# RocketometerATMega.net
KiCad netlist of a schematic drawn in EAGLE
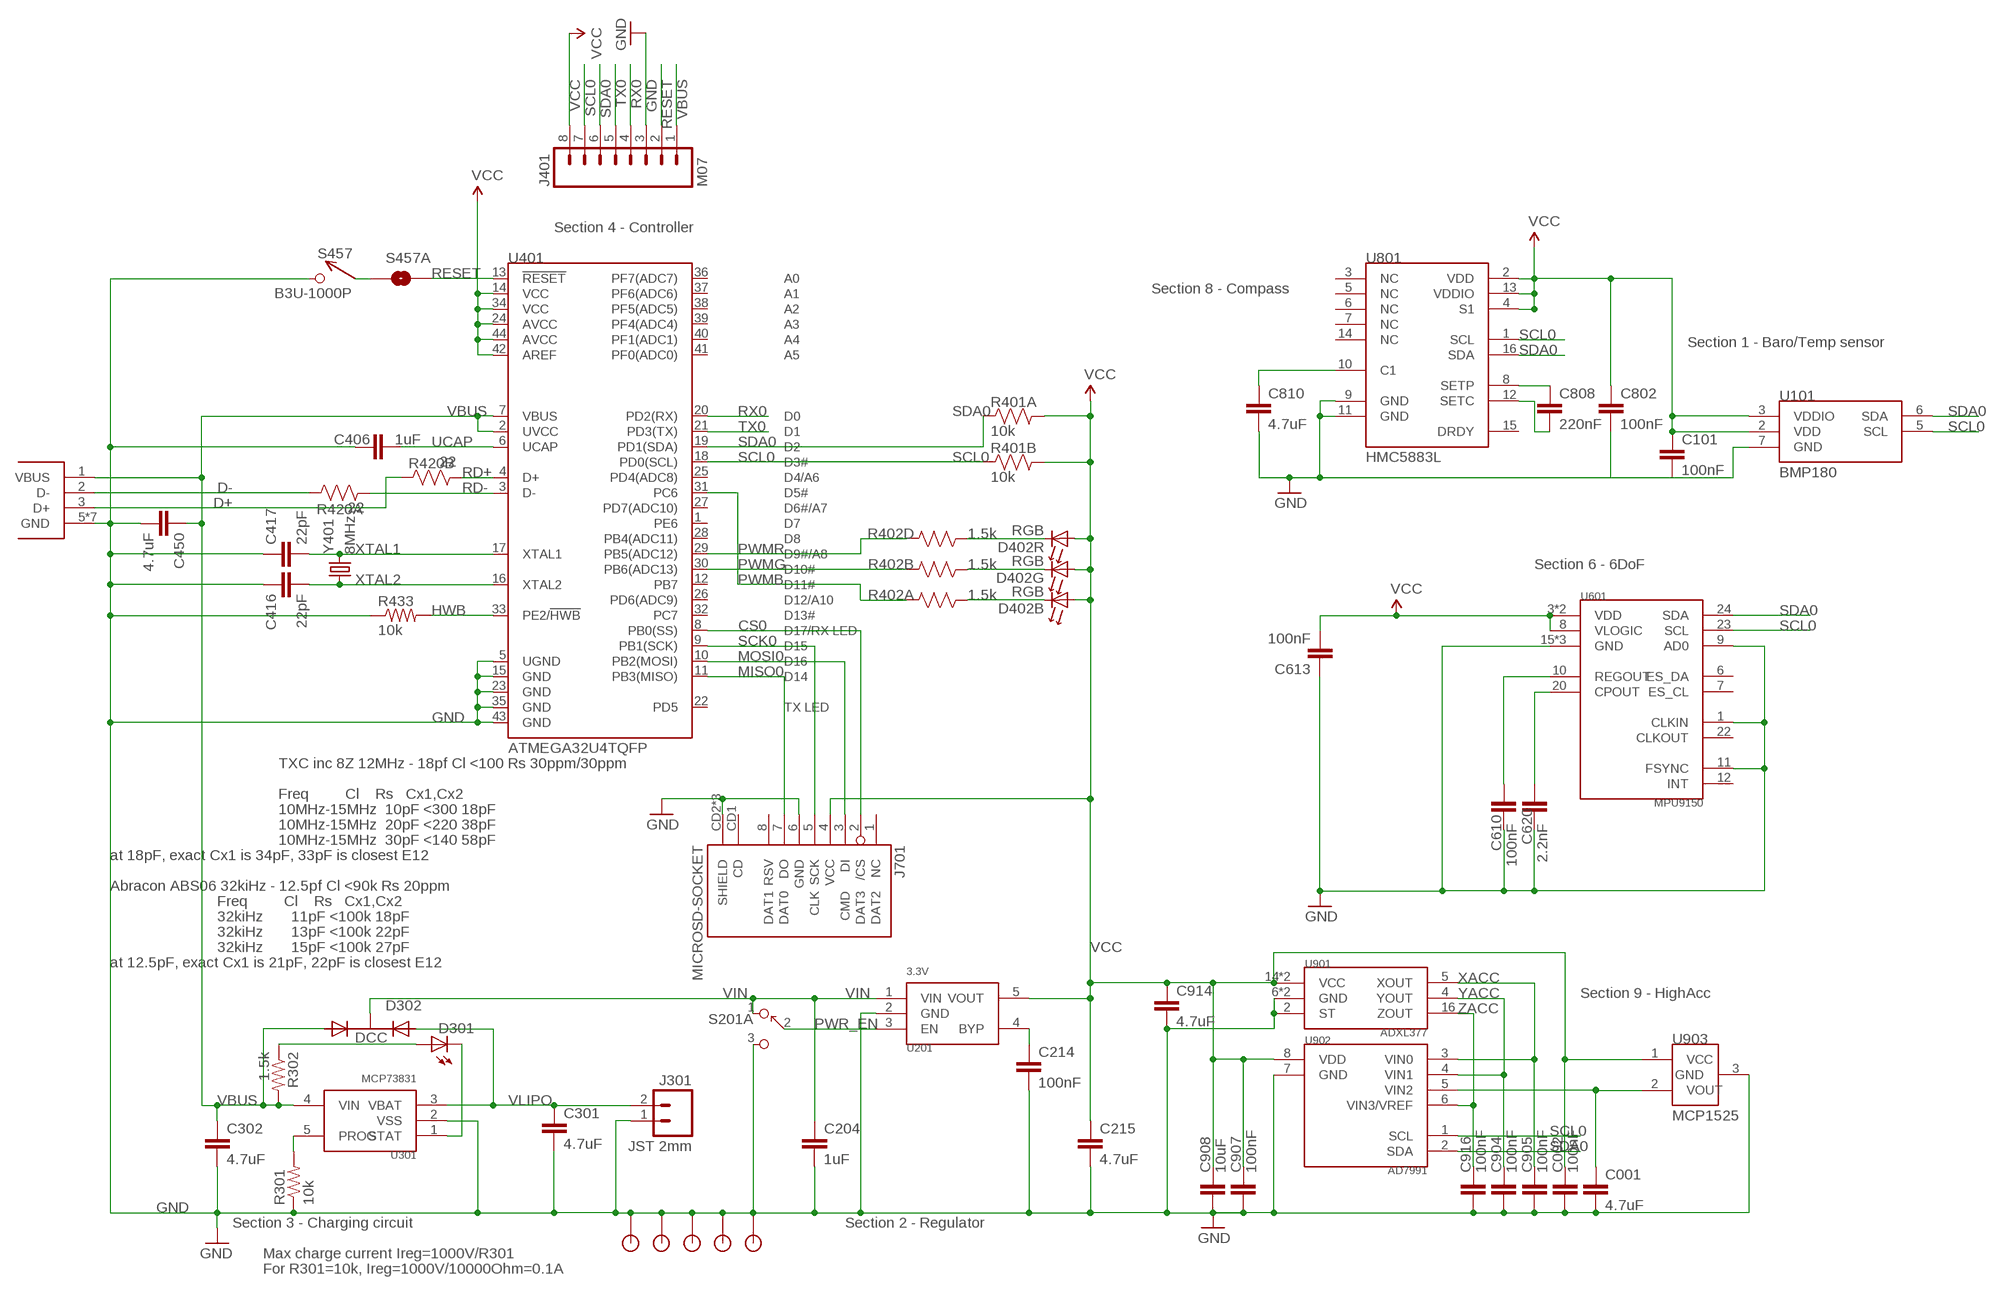
[diagram p0: schematic, sheet 1]

(export (version "E")
  (design (tool "Eeschema 10.0.6"))
  (components
    (comp (ref "C001")
      (value "4.7uF")
      (footprint "eagle-import:0402-CAP")
      (libsource (lib "eagle-import") (part "CAP0402-CAP"))
    )
    (comp (ref "C002")
      (value "100nF")
      (footprint "eagle-import:0402-CAP")
      (libsource (lib "eagle-import") (part "SparkFun-Passives_CAP0402-CAP"))
    )
    (comp (ref "C101")
      (value "100nF")
      (footprint "eagle-import:0402-CAP")
      (libsource (lib "eagle-import") (part "CAP0402-CAP"))
    )
    (comp (ref "C204")
      (value "1uF")
      (footprint "eagle-import:0402-CAP")
      (libsource (lib "eagle-import") (part "CAP0402-CAP"))
    )
    (comp (ref "C214")
      (value "100nF")
      (footprint "eagle-import:0402-CAP")
      (libsource (lib "eagle-import") (part "CAP0402-CAP"))
    )
    (comp (ref "C215")
      (value "4.7uF")
      (footprint "eagle-import:0402-CAP")
      (libsource (lib "eagle-import") (part "CAP0402-CAP"))
    )
    (comp (ref "C301")
      (value "4.7uF")
      (footprint "eagle-import:0402-CAP")
      (libsource (lib "eagle-import") (part "CAP0402-CAP"))
    )
    (comp (ref "C302")
      (value "4.7uF")
      (footprint "eagle-import:0402-CAP")
      (libsource (lib "eagle-import") (part "CAP0402-CAP"))
    )
    (comp (ref "C406")
      (value "1uF")
      (footprint "eagle-import:0402-CAP")
      (libsource (lib "eagle-import") (part "SparkFun-Passives_CAP0402-CAP"))
    )
    (comp (ref "C416")
      (value "22pF")
      (footprint "eagle-import:0402-CAP")
      (libsource (lib "eagle-import") (part "CAP0402-CAP"))
    )
    (comp (ref "C417")
      (value "22pF")
      (footprint "eagle-import:0402-CAP")
      (libsource (lib "eagle-import") (part "CAP0402-CAP"))
    )
    (comp (ref "C450")
      (value "4.7uF")
      (footprint "eagle-import:0402-CAP")
      (libsource (lib "eagle-import") (part "SparkFun-Passives_CAP0402-CAP"))
    )
    (comp (ref "C610")
      (value "100nF")
      (footprint "eagle-import:0402-CAP")
      (libsource (lib "eagle-import") (part "CAP0402-CAP"))
    )
    (comp (ref "C613")
      (value "100nF")
      (footprint "eagle-import:0402-CAP")
      (libsource (lib "eagle-import") (part "CAP0402-CAP"))
    )
    (comp (ref "C620")
      (value "2.2nF")
      (footprint "eagle-import:0402-CAP")
      (libsource (lib "eagle-import") (part "CAP0402-CAP"))
    )
    (comp (ref "C802")
      (value "100nF")
      (footprint "eagle-import:0402-CAP")
      (libsource (lib "eagle-import") (part "CAP0402-CAP"))
    )
    (comp (ref "C808")
      (value "220nF")
      (footprint "eagle-import:0402-CAP")
      (libsource (lib "eagle-import") (part "CAP0402-CAP"))
    )
    (comp (ref "C810")
      (value "4.7uF")
      (footprint "eagle-import:0402-CAP")
      (libsource (lib "eagle-import") (part "CAP0402-CAP"))
    )
    (comp (ref "C904")
      (value "100nF")
      (footprint "eagle-import:0402-CAP")
      (libsource (lib "eagle-import") (part "CAP0402-CAP"))
    )
    (comp (ref "C905")
      (value "100nF")
      (footprint "eagle-import:0402-CAP")
      (libsource (lib "eagle-import") (part "CAP0402-CAP"))
    )
    (comp (ref "C907")
      (value "100nF")
      (footprint "eagle-import:0402-CAP")
      (libsource (lib "eagle-import") (part "SparkFun-Passives_CAP0402-CAP"))
    )
    (comp (ref "C908")
      (value "10uF")
      (footprint "eagle-import:0603-CAP")
      (libsource (lib "eagle-import") (part "CAP0603-CAP"))
    )
    (comp (ref "C914")
      (value "4.7uF")
      (footprint "eagle-import:0402-CAP")
      (libsource (lib "eagle-import") (part "CAP0402-CAP"))
    )
    (comp (ref "C916")
      (value "100nF")
      (footprint "eagle-import:0402-CAP")
      (libsource (lib "eagle-import") (part "CAP0402-CAP"))
    )
    (comp (ref "D301")
      (value "YELLOW")
      (footprint "eagle-import:LED-0603")
      (libsource (lib "eagle-import") (part "LED0603"))
    )
    (comp (ref "D302")
      (value "DCC")
      (footprint "eagle-import:SOT-23-3")
      (libsource (lib "eagle-import") (part "PMEG2005CT"))
    )
    (comp (ref "D402")
      (value "RGB")
      (footprint "eagle-import:SMLP36")
      (fields (field (name "DIGIKEY") "846-1097-1-ND"))
      (libsource (lib "eagle-import") (part "SMLP36RGB2W(R)"))
    )
    (comp (ref "J301")
      (value "JST 2mm")
      (footprint "eagle-import:JST-2-SMD")
      (libsource (lib "eagle-import") (part "M02-JST-2MM-SMT"))
    )
    (comp (ref "J400")
      (value "USB_MICROB_JSTGCT")
      (footprint "eagle-import:USB_MICROB_3075")
      (libsource (lib "eagle-import") (part "USB_MICROB_JSTGCT"))
    )
    (comp (ref "J401")
      (value "M07")
      (footprint "eagle-import:1X08")
      (libsource (lib "eagle-import") (part "M081X08"))
    )
    (comp (ref "J701")
      (value "MICROSD-SOCKET")
      (footprint "eagle-import:MICROSD-SOCKET-PP")
      (libsource (lib "eagle-import") (part "MICROSD-SOCKET"))
    )
    (comp (ref "JP1")
      (value "STANDOFF")
      (footprint "eagle-import:STANDOFF")
      (libsource (lib "eagle-import") (part "STANDOFF"))
    )
    (comp (ref "JP2")
      (value "STANDOFF")
      (footprint "eagle-import:STANDOFF")
      (libsource (lib "eagle-import") (part "STANDOFF"))
    )
    (comp (ref "JP3")
      (value "STANDOFF")
      (footprint "eagle-import:STANDOFF")
      (libsource (lib "eagle-import") (part "STANDOFF"))
    )
    (comp (ref "JP4")
      (value "STANDOFF")
      (footprint "eagle-import:STANDOFF")
      (libsource (lib "eagle-import") (part "STANDOFF"))
    )
    (comp (ref "JP5")
      (value "STANDOFF")
      (footprint "eagle-import:STANDOFF")
      (libsource (lib "eagle-import") (part "STANDOFF"))
    )
    (comp (ref "R301")
      (value "10k")
      (footprint "eagle-import:0402-RES")
      (libsource (lib "eagle-import") (part "RESISTOR0402-RES"))
    )
    (comp (ref "R302")
      (value "1.5k")
      (footprint "eagle-import:0402-RES")
      (libsource (lib "eagle-import") (part "RESISTOR0402-RES"))
    )
    (comp (ref "R401")
      (value "10k")
      (footprint "eagle-import:CRA02")
      (fields (field (name "DIGIKEY") "Y5103CT-ND"))
      (libsource (lib "eagle-import") (part "RP2EXB24V"))
    )
    (comp (ref "R402")
      (value "1.5k")
      (footprint "eagle-import:CRA04")
      (fields (field (name "DIGIKEY") "CRA4S81.5KCT-ND"))
      (libsource (lib "eagle-import") (part "RP404"))
    )
    (comp (ref "R420")
      (value "22")
      (footprint "eagle-import:CRA02")
      (fields (field (name "DIGIKEY") "Y5220CT-ND"))
      (libsource (lib "eagle-import") (part "RP2EXB24V"))
    )
    (comp (ref "R433")
      (value "10k")
      (footprint "eagle-import:0402-RES")
      (libsource (lib "eagle-import") (part "SparkFun-Passives_RESISTOR0402-RES"))
    )
    (comp (ref "S201")
      (value "AYZ0202")
      (footprint "eagle-import:AYZ0202")
      (libsource (lib "eagle-import") (part "AYZ0202"))
    )
    (comp (ref "S457")
      (value "B3U-1000P")
      (footprint "eagle-import:B3U-1000P")
      (libsource (lib "eagle-import") (part "B3U-1000P"))
    )
    (comp (ref "S457A")
      (value "SOLDERJUMPERNO")
      (footprint "eagle-import:SJ_2S-NO")
      (libsource (lib "eagle-import") (part "SOLDERJUMPERNO"))
    )
    (comp (ref "U101")
      (value "BMP180")
      (footprint "eagle-import:BMP180")
      (libsource (lib "eagle-import") (part "BMP180"))
    )
    (comp (ref "U201")
      (value "3.3V")
      (footprint "eagle-import:SOT-23-5")
      (libsource (lib "eagle-import") (part "MIC5319D5"))
    )
    (comp (ref "U301")
      (value "MCP73831")
      (footprint "eagle-import:SOT-23-5")
      (libsource (lib "eagle-import") (part "MCP73831"))
    )
    (comp (ref "U401")
      (value "ATMEGA32U4TQFP")
      (footprint "eagle-import:SPARKFUN-DIGITALIC_TQFP44")
      (libsource (lib "eagle-import") (part "ATMEGA32U4TQFP"))
    )
    (comp (ref "U601")
      (value "MPU9150")
      (footprint "eagle-import:LLGA24")
      (libsource (lib "eagle-import") (part "MPU9150"))
    )
    (comp (ref "U801")
      (value "HMC5883L")
      (footprint "eagle-import:16LPCC")
      (libsource (lib "eagle-import") (part "HMC5883LSMD"))
    )
    (comp (ref "U901")
      (value "ADXL377")
      (footprint "eagle-import:ADXL377")
      (libsource (lib "eagle-import") (part "ADXL377"))
    )
    (comp (ref "U902")
      (value "AD7991")
      (footprint "eagle-import:SOT-23-8")
      (libsource (lib "eagle-import") (part "AD799X"))
    )
    (comp (ref "U903")
      (value "MCP1525")
      (footprint "eagle-import:SOT-23-3")
      (libsource (lib "eagle-import") (part "MCP1525"))
    )
    (comp (ref "Y401")
      (value "8MHz")
      (footprint "eagle-import:CRYSTAL_SMD_3_2MM_2_5MM")
      (libsource (lib "eagle-import") (part "NX3225GD"))
    )
  )
  (nets
    (net (code "1") (name "/CS0") (class "Default")
      (node (ref "J701") (pin "2") (pinfunction "/CS_2") (pintype "bidirectional"))
      (node (ref "U401") (pin "8") (pinfunction "PB0(SS)_8") (pintype "bidirectional"))
    )
    (net (code "2") (name "/D+") (class "Default")
      (node (ref "J400") (pin "3") (pinfunction "D+_3") (pintype "bidirectional"))
      (node (ref "R420") (pin "2") (pinfunction "1_2") (pintype "passive"))
    )
    (net (code "3") (name "/D-") (class "Default")
      (node (ref "J400") (pin "2") (pinfunction "D-_2") (pintype "bidirectional"))
      (node (ref "R420") (pin "1") (pinfunction "1_1") (pintype "passive"))
    )
    (net (code "4") (name "/HWB") (class "Default")
      (node (ref "R433") (pin "2") (pinfunction "2_2") (pintype "passive"))
      (node (ref "U401") (pin "33") (pinfunction "PE2/~{HWB}_33") (pintype "bidirectional"))
    )
    (net (code "5") (name "/MISO0") (class "Default")
      (node (ref "J701") (pin "7") (pinfunction "DO_7") (pintype "bidirectional"))
      (node (ref "U401") (pin "11") (pinfunction "PB3(MISO)_11") (pintype "bidirectional"))
    )
    (net (code "6") (name "/MOSI0") (class "Default")
      (node (ref "J701") (pin "3") (pinfunction "DI_3") (pintype "bidirectional"))
      (node (ref "U401") (pin "10") (pinfunction "PB2(MOSI)_10") (pintype "bidirectional"))
    )
    (net (code "7") (name "/PWMB") (class "Default")
      (node (ref "R402") (pin "8") (pinfunction "2_8") (pintype "passive"))
      (node (ref "U401") (pin "31") (pinfunction "PC6_31") (pintype "bidirectional"))
    )
    (net (code "8") (name "/PWMG") (class "Default")
      (node (ref "R402") (pin "7") (pinfunction "2_7") (pintype "passive"))
      (node (ref "U401") (pin "30") (pinfunction "PB6(ADC13)_30") (pintype "bidirectional"))
    )
    (net (code "9") (name "/PWMR") (class "Default")
      (node (ref "R402") (pin "5") (pinfunction "2_5") (pintype "passive"))
      (node (ref "U401") (pin "29") (pinfunction "PB5(ADC12)_29") (pintype "bidirectional"))
    )
    (net (code "10") (name "/PWR_EN") (class "Default")
      (node (ref "S201") (pin "2") (pinfunction "P$3_2") (pintype "bidirectional"))
      (node (ref "U201") (pin "3") (pinfunction "EN_3") (pintype "bidirectional"))
    )
    (net (code "11") (name "/RD+") (class "Default")
      (node (ref "R420") (pin "3") (pinfunction "2_3") (pintype "passive"))
      (node (ref "U401") (pin "4") (pinfunction "D+_4") (pintype "bidirectional"))
    )
    (net (code "12") (name "/RD-") (class "Default")
      (node (ref "R420") (pin "4") (pinfunction "2_4") (pintype "passive"))
      (node (ref "U401") (pin "3") (pinfunction "D-_3") (pintype "bidirectional"))
    )
    (net (code "13") (name "/RESET") (class "Default")
      (node (ref "J401") (pin "2") (pinfunction "2_2") (pintype "passive"))
      (node (ref "S457A") (pin "2") (pinfunction "2_2") (pintype "passive"))
      (node (ref "U401") (pin "13") (pinfunction "~{RESET}_13") (pintype "bidirectional"))
    )
    (net (code "14") (name "/RX0") (class "Default")
      (node (ref "J401") (pin "4") (pinfunction "4_4") (pintype "passive"))
      (node (ref "U401") (pin "20") (pinfunction "PD2(RX)_20") (pintype "bidirectional"))
    )
    (net (code "15") (name "/SCK0") (class "Default")
      (node (ref "J701") (pin "5") (pinfunction "SCK_5") (pintype "bidirectional"))
      (node (ref "U401") (pin "9") (pinfunction "PB1(SCK)_9") (pintype "bidirectional"))
    )
    (net (code "16") (name "/SCL0") (class "Default")
      (node (ref "J401") (pin "7") (pinfunction "7_7") (pintype "passive"))
      (node (ref "R401") (pin "2") (pinfunction "1_2") (pintype "passive"))
      (node (ref "U101") (pin "5") (pinfunction "SCL_5") (pintype "input"))
      (node (ref "U401") (pin "18") (pinfunction "PD0(SCL)_18") (pintype "bidirectional"))
      (node (ref "U601") (pin "23") (pinfunction "SCL_23") (pintype "bidirectional"))
      (node (ref "U801") (pin "1") (pinfunction "SCL_1") (pintype "bidirectional"))
      (node (ref "U902") (pin "1") (pinfunction "SCL_1") (pintype "bidirectional"))
    )
    (net (code "17") (name "/SDA0") (class "Default")
      (node (ref "J401") (pin "6") (pinfunction "6_6") (pintype "passive"))
      (node (ref "R401") (pin "1") (pinfunction "1_1") (pintype "passive"))
      (node (ref "U101") (pin "6") (pinfunction "SDA_6") (pintype "bidirectional"))
      (node (ref "U401") (pin "19") (pinfunction "PD1(SDA)_19") (pintype "bidirectional"))
      (node (ref "U601") (pin "24") (pinfunction "SDA_24") (pintype "bidirectional"))
      (node (ref "U801") (pin "16") (pinfunction "SDA_16") (pintype "bidirectional"))
      (node (ref "U902") (pin "2") (pinfunction "SDA_2") (pintype "bidirectional"))
    )
    (net (code "18") (name "/TX0") (class "Default")
      (node (ref "J401") (pin "5") (pinfunction "5_5") (pintype "passive"))
      (node (ref "U401") (pin "21") (pinfunction "PD3(TX)_21") (pintype "bidirectional"))
    )
    (net (code "19") (name "/UCAP") (class "Default")
      (node (ref "C406") (pin "1") (pinfunction "1_1") (pintype "passive"))
      (node (ref "U401") (pin "6") (pinfunction "UCAP_6") (pintype "bidirectional"))
    )
    (net (code "20") (name "/VBUS") (class "Default")
      (node (ref "C302") (pin "1") (pinfunction "1_1") (pintype "passive"))
      (node (ref "C450") (pin "1") (pinfunction "1_1") (pintype "passive"))
      (node (ref "D302") (pin "1") (pinfunction "A1_1") (pintype "passive"))
      (node (ref "J400") (pin "1") (pinfunction "VBUS_1") (pintype "bidirectional"))
      (node (ref "J401") (pin "1") (pinfunction "1_1") (pintype "passive"))
      (node (ref "R302") (pin "2") (pinfunction "2_2") (pintype "passive"))
      (node (ref "U301") (pin "4") (pinfunction "VIN_4") (pintype "power_in"))
      (node (ref "U401") (pin "2") (pinfunction "UVCC_2") (pintype "bidirectional"))
      (node (ref "U401") (pin "7") (pinfunction "VBUS_7") (pintype "bidirectional"))
    )
    (net (code "21") (name "/VIN") (class "Default")
      (node (ref "C204") (pin "1") (pinfunction "1_1") (pintype "passive"))
      (node (ref "D302") (pin "3") (pinfunction "K_3") (pintype "passive"))
      (node (ref "S201") (pin "1") (pinfunction "P$1_1") (pintype "bidirectional"))
      (node (ref "U201") (pin "1") (pinfunction "VIN_1") (pintype "bidirectional"))
    )
    (net (code "22") (name "/VLIPO") (class "Default")
      (node (ref "C301") (pin "1") (pinfunction "1_1") (pintype "passive"))
      (node (ref "D302") (pin "2") (pinfunction "A2_2") (pintype "passive"))
      (node (ref "J301") (pin "2") (pinfunction "2_2") (pintype "passive"))
      (node (ref "U301") (pin "3") (pinfunction "VBAT_3") (pintype "power_in"))
    )
    (net (code "23") (name "/XACC") (class "Default")
      (node (ref "C905") (pin "1") (pinfunction "1_1") (pintype "passive"))
      (node (ref "U901") (pin "5") (pinfunction "XOUT_5") (pintype "bidirectional"))
      (node (ref "U902") (pin "3") (pinfunction "VIN0_3") (pintype "bidirectional"))
    )
    (net (code "24") (name "/XTAL1") (class "Default")
      (node (ref "C417") (pin "2") (pinfunction "2_2") (pintype "passive"))
      (node (ref "U401") (pin "17") (pinfunction "XTAL1_17") (pintype "bidirectional"))
      (node (ref "Y401") (pin "2") (pinfunction "2_2") (pintype "passive"))
    )
    (net (code "25") (name "/XTAL2") (class "Default")
      (node (ref "C416") (pin "2") (pinfunction "2_2") (pintype "passive"))
      (node (ref "U401") (pin "16") (pinfunction "XTAL2_16") (pintype "bidirectional"))
      (node (ref "Y401") (pin "1") (pinfunction "1_1") (pintype "passive"))
    )
    (net (code "26") (name "/YACC") (class "Default")
      (node (ref "C904") (pin "1") (pinfunction "1_1") (pintype "passive"))
      (node (ref "U901") (pin "4") (pinfunction "YOUT_4") (pintype "bidirectional"))
      (node (ref "U902") (pin "4") (pinfunction "VIN1_4") (pintype "bidirectional"))
    )
    (net (code "27") (name "/ZACC") (class "Default")
      (node (ref "C916") (pin "1") (pinfunction "1_1") (pintype "passive"))
      (node (ref "U901") (pin "16") (pinfunction "ZOUT_16") (pintype "bidirectional"))
      (node (ref "U902") (pin "6") (pinfunction "VIN3/VREF_6") (pintype "bidirectional"))
    )
    (net (code "28") (name "GND") (class "Default")
      (node (ref "C001") (pin "2") (pinfunction "2_2") (pintype "passive"))
      (node (ref "C002") (pin "2") (pinfunction "2_2") (pintype "passive"))
      (node (ref "C101") (pin "2") (pinfunction "2_2") (pintype "passive"))
      (node (ref "C204") (pin "2") (pinfunction "2_2") (pintype "passive"))
      (node (ref "C214") (pin "2") (pinfunction "2_2") (pintype "passive"))
      (node (ref "C215") (pin "2") (pinfunction "2_2") (pintype "passive"))
      (node (ref "C301") (pin "2") (pinfunction "2_2") (pintype "passive"))
      (node (ref "C302") (pin "2") (pinfunction "2_2") (pintype "passive"))
      (node (ref "C406") (pin "2") (pinfunction "2_2") (pintype "passive"))
      (node (ref "C416") (pin "1") (pinfunction "1_1") (pintype "passive"))
      (node (ref "C417") (pin "1") (pinfunction "1_1") (pintype "passive"))
      (node (ref "C450") (pin "2") (pinfunction "2_2") (pintype "passive"))
      (node (ref "C610") (pin "2") (pinfunction "2_2") (pintype "passive"))
      (node (ref "C613") (pin "1") (pinfunction "1_1") (pintype "passive"))
      (node (ref "C620") (pin "1") (pinfunction "1_1") (pintype "passive"))
      (node (ref "C802") (pin "2") (pinfunction "2_2") (pintype "passive"))
      (node (ref "C810") (pin "2") (pinfunction "2_2") (pintype "passive"))
      (node (ref "C904") (pin "2") (pinfunction "2_2") (pintype "passive"))
      (node (ref "C905") (pin "2") (pinfunction "2_2") (pintype "passive"))
      (node (ref "C907") (pin "2") (pinfunction "2_2") (pintype "passive"))
      (node (ref "C908") (pin "2") (pinfunction "2_2") (pintype "passive"))
      (node (ref "C914") (pin "2") (pinfunction "2_2") (pintype "passive"))
      (node (ref "C916") (pin "2") (pinfunction "2_2") (pintype "passive"))
      (node (ref "J301") (pin "1") (pinfunction "1_1") (pintype "passive"))
      (node (ref "J400") (pin "5") (pinfunction "GND_5") (pintype "bidirectional"))
      (node (ref "J400") (pin "P$1") (pinfunction "GND_P$1") (pintype "bidirectional"))
      (node (ref "J400") (pin "P$10") (pinfunction "GND_P$10") (pintype "bidirectional"))
      (node (ref "J400") (pin "P$2") (pinfunction "GND_P$2") (pintype "bidirectional"))
      (node (ref "J400") (pin "P$3") (pinfunction "GND_P$3") (pintype "bidirectional"))
      (node (ref "J400") (pin "P$4") (pinfunction "GND_P$4") (pintype "bidirectional"))
      (node (ref "J400") (pin "P$8") (pinfunction "GND_P$8") (pintype "bidirectional"))
      (node (ref "J401") (pin "3") (pinfunction "3_3") (pintype "passive"))
      (node (ref "J701") (pin "6") (pinfunction "GND_6") (pintype "bidirectional"))
      (node (ref "J701") (pin "CD2") (pinfunction "SHIELD_CD2") (pintype "bidirectional"))
      (node (ref "J701") (pin "GND1") (pinfunction "SHIELD_GND1") (pintype "bidirectional"))
      (node (ref "J701") (pin "GND3") (pinfunction "SHIELD_GND3") (pintype "bidirectional"))
      (node (ref "JP1") (pin "P$1") (pinfunction "P$1_P$1") (pintype "bidirectional"))
      (node (ref "JP2") (pin "P$1") (pinfunction "P$1_P$1") (pintype "bidirectional"))
      (node (ref "JP3") (pin "P$1") (pinfunction "P$1_P$1") (pintype "bidirectional"))
      (node (ref "JP4") (pin "P$1") (pinfunction "P$1_P$1") (pintype "bidirectional"))
      (node (ref "JP5") (pin "P$1") (pinfunction "P$1_P$1") (pintype "bidirectional"))
      (node (ref "R301") (pin "1") (pinfunction "1_1") (pintype "passive"))
      (node (ref "R433") (pin "1") (pinfunction "1_1") (pintype "passive"))
      (node (ref "S201") (pin "3") (pinfunction "P$2_3") (pintype "bidirectional"))
      (node (ref "S457") (pin "P$2") (pinfunction "2_P$2") (pintype "bidirectional"))
      (node (ref "U101") (pin "7") (pinfunction "GND_7") (pintype "power_in"))
      (node (ref "U201") (pin "2") (pinfunction "GND_2") (pintype "bidirectional"))
      (node (ref "U301") (pin "2") (pinfunction "VSS_2") (pintype "power_in"))
      (node (ref "U401") (pin "15") (pinfunction "GND_15") (pintype "bidirectional"))
      (node (ref "U401") (pin "23") (pinfunction "GND_23") (pintype "bidirectional"))
      (node (ref "U401") (pin "35") (pinfunction "GND_35") (pintype "bidirectional"))
      (node (ref "U401") (pin "43") (pinfunction "GND_43") (pintype "bidirectional"))
      (node (ref "U401") (pin "5") (pinfunction "UGND_5") (pintype "bidirectional"))
      (node (ref "U601") (pin "1") (pinfunction "CLKIN_1") (pintype "bidirectional"))
      (node (ref "U601") (pin "11") (pinfunction "FSYNC_11") (pintype "bidirectional"))
      (node (ref "U601") (pin "15") (pinfunction "GND_15") (pintype "bidirectional"))
      (node (ref "U601") (pin "17") (pinfunction "GND_17") (pintype "bidirectional"))
      (node (ref "U601") (pin "18") (pinfunction "GND_18") (pintype "bidirectional"))
      (node (ref "U601") (pin "9") (pinfunction "AD0_9") (pintype "bidirectional"))
      (node (ref "U801") (pin "11") (pinfunction "GND_11") (pintype "bidirectional"))
      (node (ref "U801") (pin "9") (pinfunction "GND_9") (pintype "bidirectional"))
      (node (ref "U901") (pin "2") (pinfunction "ST_2") (pintype "bidirectional"))
      (node (ref "U901") (pin "6") (pinfunction "GND_6") (pintype "bidirectional"))
      (node (ref "U901") (pin "7") (pinfunction "GND_7") (pintype "bidirectional"))
      (node (ref "U902") (pin "7") (pinfunction "GND_7") (pintype "bidirectional"))
      (node (ref "U903") (pin "3") (pinfunction "GND_3") (pintype "bidirectional"))
    )
    (net (code "29") (name "Net-(D301-PadA)") (class "Default")
      (node (ref "D301") (pin "A") (pinfunction "A_A") (pintype "passive"))
      (node (ref "R302") (pin "1") (pinfunction "1_1") (pintype "passive"))
    )
    (net (code "30") (name "Net-(D402A-C)") (class "Default")
      (node (ref "D402") (pin "1") (pinfunction "C_1") (pintype "passive"))
      (node (ref "R402") (pin "1") (pinfunction "1_1") (pintype "passive"))
    )
    (net (code "31") (name "Net-(D402B-C)") (class "Default")
      (node (ref "D402") (pin "3") (pinfunction "C_3") (pintype "passive"))
      (node (ref "R402") (pin "2") (pinfunction "1_2") (pintype "passive"))
    )
    (net (code "32") (name "Net-(D402C-C)") (class "Default")
      (node (ref "D402") (pin "5") (pinfunction "C_5") (pintype "passive"))
      (node (ref "R402") (pin "4") (pinfunction "1_4") (pintype "passive"))
    )
    (net (code "33") (name "Net-(S457-1)") (class "Default")
      (node (ref "S457") (pin "P$1") (pinfunction "1_P$1") (pintype "bidirectional"))
      (node (ref "S457A") (pin "1") (pinfunction "1_1") (pintype "passive"))
    )
    (net (code "34") (name "Net-(U201-BYP)") (class "Default")
      (node (ref "C214") (pin "1") (pinfunction "1_1") (pintype "passive"))
      (node (ref "U201") (pin "4") (pinfunction "BYP_4") (pintype "bidirectional"))
    )
    (net (code "35") (name "Net-(U301-PROG)") (class "Default")
      (node (ref "R301") (pin "2") (pinfunction "2_2") (pintype "passive"))
      (node (ref "U301") (pin "5") (pinfunction "PROG_5") (pintype "passive"))
    )
    (net (code "36") (name "Net-(U301-STAT)") (class "Default")
      (node (ref "D301") (pin "C") (pinfunction "C_C") (pintype "passive"))
      (node (ref "U301") (pin "1") (pinfunction "STAT_1") (pintype "bidirectional"))
    )
    (net (code "37") (name "Net-(U601-CPOUT)") (class "Default")
      (node (ref "C620") (pin "2") (pinfunction "2_2") (pintype "passive"))
      (node (ref "U601") (pin "20") (pinfunction "CPOUT_20") (pintype "bidirectional"))
    )
    (net (code "38") (name "Net-(U601-REGOUT)") (class "Default")
      (node (ref "C610") (pin "1") (pinfunction "1_1") (pintype "passive"))
      (node (ref "U601") (pin "10") (pinfunction "REGOUT_10") (pintype "bidirectional"))
    )
    (net (code "39") (name "Net-(U801-C1)") (class "Default")
      (node (ref "C810") (pin "1") (pinfunction "1_1") (pintype "passive"))
      (node (ref "U801") (pin "10") (pinfunction "C1_10") (pintype "bidirectional"))
    )
    (net (code "40") (name "Net-(U801-SETC)") (class "Default")
      (node (ref "C808") (pin "2") (pinfunction "2_2") (pintype "passive"))
      (node (ref "U801") (pin "12") (pinfunction "SETC_12") (pintype "bidirectional"))
    )
    (net (code "41") (name "Net-(U801-SETP)") (class "Default")
      (node (ref "C808") (pin "1") (pinfunction "1_1") (pintype "passive"))
      (node (ref "U801") (pin "8") (pinfunction "SETP_8") (pintype "bidirectional"))
    )
    (net (code "42") (name "Net-(U902-VIN2)") (class "Default")
      (node (ref "C001") (pin "1") (pinfunction "1_1") (pintype "passive"))
      (node (ref "U902") (pin "5") (pinfunction "VIN2_5") (pintype "bidirectional"))
      (node (ref "U903") (pin "2") (pinfunction "VOUT_2") (pintype "bidirectional"))
    )
    (net (code "43") (name "VCC") (class "Default")
      (node (ref "C002") (pin "1") (pinfunction "1_1") (pintype "passive"))
      (node (ref "C101") (pin "1") (pinfunction "1_1") (pintype "passive"))
      (node (ref "C215") (pin "1") (pinfunction "1_1") (pintype "passive"))
      (node (ref "C613") (pin "2") (pinfunction "2_2") (pintype "passive"))
      (node (ref "C802") (pin "1") (pinfunction "1_1") (pintype "passive"))
      (node (ref "C907") (pin "1") (pinfunction "1_1") (pintype "passive"))
      (node (ref "C908") (pin "1") (pinfunction "1_1") (pintype "passive"))
      (node (ref "C914") (pin "1") (pinfunction "1_1") (pintype "passive"))
      (node (ref "D402") (pin "2") (pinfunction "A_2") (pintype "passive"))
      (node (ref "D402") (pin "4") (pinfunction "A_4") (pintype "passive"))
      (node (ref "D402") (pin "6") (pinfunction "A_6") (pintype "passive"))
      (node (ref "J401") (pin "8") (pinfunction "8_8") (pintype "passive"))
      (node (ref "J701") (pin "4") (pinfunction "VCC_4") (pintype "bidirectional"))
      (node (ref "R401") (pin "3") (pinfunction "2_3") (pintype "passive"))
      (node (ref "R401") (pin "4") (pinfunction "2_4") (pintype "passive"))
      (node (ref "U101") (pin "2") (pinfunction "VDD_2") (pintype "power_in"))
      (node (ref "U101") (pin "3") (pinfunction "VDDIO_3") (pintype "power_in"))
      (node (ref "U201") (pin "5") (pinfunction "VOUT_5") (pintype "bidirectional"))
      (node (ref "U401") (pin "14") (pinfunction "VCC_14") (pintype "bidirectional"))
      (node (ref "U401") (pin "24") (pinfunction "AVCC_24") (pintype "bidirectional"))
      (node (ref "U401") (pin "34") (pinfunction "VCC_34") (pintype "bidirectional"))
      (node (ref "U401") (pin "42") (pinfunction "AREF_42") (pintype "bidirectional"))
      (node (ref "U401") (pin "44") (pinfunction "AVCC_44") (pintype "bidirectional"))
      (node (ref "U601") (pin "13") (pinfunction "VDD_13") (pintype "bidirectional"))
      (node (ref "U601") (pin "3") (pinfunction "VDD_3") (pintype "bidirectional"))
      (node (ref "U601") (pin "8") (pinfunction "VLOGIC_8") (pintype "bidirectional"))
      (node (ref "U801") (pin "13") (pinfunction "VDDIO_13") (pintype "bidirectional"))
      (node (ref "U801") (pin "2") (pinfunction "VDD_2") (pintype "bidirectional"))
      (node (ref "U801") (pin "4") (pinfunction "S1_4") (pintype "bidirectional"))
      (node (ref "U901") (pin "14") (pinfunction "VCC_14") (pintype "bidirectional"))
      (node (ref "U901") (pin "15") (pinfunction "VCC_15") (pintype "bidirectional"))
      (node (ref "U902") (pin "8") (pinfunction "VDD_8") (pintype "bidirectional"))
      (node (ref "U903") (pin "1") (pinfunction "VCC_1") (pintype "bidirectional"))
    )
    (net (code "44") (name "unconnected-(J701-CD-PadCD1)") (class "Default")
      (node (ref "J701") (pin "CD1") (pinfunction "CD_CD1") (pintype "bidirectional"))
    )
    (net (code "45") (name "unconnected-(J701-NC-Pad1)") (class "Default")
      (node (ref "J701") (pin "1") (pinfunction "NC_1") (pintype "bidirectional"))
    )
    (net (code "46") (name "unconnected-(J701-RSV-Pad8)") (class "Default")
      (node (ref "J701") (pin "8") (pinfunction "RSV_8") (pintype "bidirectional"))
    )
    (net (code "47") (name "unconnected-(U401-PB4(ADC11)-Pad28)") (class "Default")
      (node (ref "U401") (pin "28") (pinfunction "PB4(ADC11)_28") (pintype "bidirectional"))
    )
    (net (code "48") (name "unconnected-(U401-PB7-Pad12)") (class "Default")
      (node (ref "U401") (pin "12") (pinfunction "PB7_12") (pintype "bidirectional"))
    )
    (net (code "49") (name "unconnected-(U401-PC7-Pad32)") (class "Default")
      (node (ref "U401") (pin "32") (pinfunction "PC7_32") (pintype "bidirectional"))
    )
    (net (code "50") (name "unconnected-(U401-PD4(ADC8)-Pad25)") (class "Default")
      (node (ref "U401") (pin "25") (pinfunction "PD4(ADC8)_25") (pintype "bidirectional"))
    )
    (net (code "51") (name "unconnected-(U401-PD5-Pad22)") (class "Default")
      (node (ref "U401") (pin "22") (pinfunction "PD5_22") (pintype "bidirectional"))
    )
    (net (code "52") (name "unconnected-(U401-PD6(ADC9)-Pad26)") (class "Default")
      (node (ref "U401") (pin "26") (pinfunction "PD6(ADC9)_26") (pintype "bidirectional"))
    )
    (net (code "53") (name "unconnected-(U401-PD7(ADC10)-Pad27)") (class "Default")
      (node (ref "U401") (pin "27") (pinfunction "PD7(ADC10)_27") (pintype "bidirectional"))
    )
    (net (code "54") (name "unconnected-(U401-PE6-Pad1)") (class "Default")
      (node (ref "U401") (pin "1") (pinfunction "PE6_1") (pintype "bidirectional"))
    )
    (net (code "55") (name "unconnected-(U401-PF0(ADC0)-Pad41)") (class "Default")
      (node (ref "U401") (pin "41") (pinfunction "PF0(ADC0)_41") (pintype "bidirectional"))
    )
    (net (code "56") (name "unconnected-(U401-PF1(ADC1)-Pad40)") (class "Default")
      (node (ref "U401") (pin "40") (pinfunction "PF1(ADC1)_40") (pintype "bidirectional"))
    )
    (net (code "57") (name "unconnected-(U401-PF4(ADC4)-Pad39)") (class "Default")
      (node (ref "U401") (pin "39") (pinfunction "PF4(ADC4)_39") (pintype "bidirectional"))
    )
    (net (code "58") (name "unconnected-(U401-PF5(ADC5)-Pad38)") (class "Default")
      (node (ref "U401") (pin "38") (pinfunction "PF5(ADC5)_38") (pintype "bidirectional"))
    )
    (net (code "59") (name "unconnected-(U401-PF6(ADC6)-Pad37)") (class "Default")
      (node (ref "U401") (pin "37") (pinfunction "PF6(ADC6)_37") (pintype "bidirectional"))
    )
    (net (code "60") (name "unconnected-(U401-PF7(ADC7)-Pad36)") (class "Default")
      (node (ref "U401") (pin "36") (pinfunction "PF7(ADC7)_36") (pintype "bidirectional"))
    )
    (net (code "61") (name "unconnected-(U601-CLKOUT-Pad22)") (class "Default")
      (node (ref "U601") (pin "22") (pinfunction "CLKOUT_22") (pintype "bidirectional"))
    )
    (net (code "62") (name "unconnected-(U601-ES_CL-Pad7)") (class "Default")
      (node (ref "U601") (pin "7") (pinfunction "ES_CL_7") (pintype "bidirectional"))
    )
    (net (code "63") (name "unconnected-(U601-ES_DA-Pad6)") (class "Default")
      (node (ref "U601") (pin "6") (pinfunction "ES_DA_6") (pintype "bidirectional"))
    )
    (net (code "64") (name "unconnected-(U601-INT-Pad12)") (class "Default")
      (node (ref "U601") (pin "12") (pinfunction "INT_12") (pintype "bidirectional"))
    )
    (net (code "65") (name "unconnected-(U801-DRDY-Pad15)") (class "Default")
      (node (ref "U801") (pin "15") (pinfunction "DRDY_15") (pintype "bidirectional"))
    )
    (net (code "66") (name "unconnected-(U801-NC-Pad3)") (class "Default")
      (node (ref "U801") (pin "3") (pinfunction "NC_3") (pintype "bidirectional"))
    )
    (net (code "67") (name "unconnected-(U801-NC-Pad5)") (class "Default")
      (node (ref "U801") (pin "5") (pinfunction "NC_5") (pintype "bidirectional"))
    )
    (net (code "68") (name "unconnected-(U801-NC-Pad6)") (class "Default")
      (node (ref "U801") (pin "6") (pinfunction "NC_6") (pintype "bidirectional"))
    )
    (net (code "69") (name "unconnected-(U801-NC-Pad7)") (class "Default")
      (node (ref "U801") (pin "7") (pinfunction "NC_7") (pintype "bidirectional"))
    )
    (net (code "70") (name "unconnected-(U801-NC-Pad14)") (class "Default")
      (node (ref "U801") (pin "14") (pinfunction "NC_14") (pintype "bidirectional"))
    )
  )
)
